# main.net
KiCad netlist of a schematic drawn in EAGLE
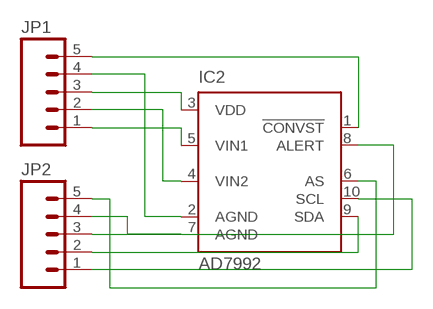
[diagram p0: schematic, sheet 1]

(export (version "E")
  (design (tool "Eeschema 10.0.6"))
  (components
    (comp (ref "IC2")
      (value "AD7992")
      (footprint "eagle-import:MSOP10")
      (fields (field (name "MPN") "AD7992BRMZ-0"))
      (libsource (lib "eagle-import") (part "AD7992"))
    )
    (comp (ref "JP1")
      (value "M05PTH_LONGPADS")
      (footprint "eagle-import:1X05_LONGPADS")
      (libsource (lib "eagle-import") (part "M05PTH_LONGPADS"))
    )
    (comp (ref "JP2")
      (value "M05PTH_LONGPADS")
      (footprint "eagle-import:1X05_LONGPADS")
      (libsource (lib "eagle-import") (part "M05PTH_LONGPADS"))
    )
  )
  (nets
    (net (code "1") (name "Net-(IC2-AGND-Pad2)") (class "Default")
      (node (ref "IC2") (pin "2") (pinfunction "AGND_2") (pintype "power_in"))
      (node (ref "JP1") (pin "4") (pinfunction "4_4") (pintype "passive"))
    )
    (net (code "2") (name "Net-(IC2-AGND-Pad7)") (class "Default")
      (node (ref "IC2") (pin "7") (pinfunction "AGND_7") (pintype "power_in"))
      (node (ref "JP2") (pin "4") (pinfunction "4_4") (pintype "passive"))
    )
    (net (code "3") (name "Net-(IC2-ALERT)") (class "Default")
      (node (ref "IC2") (pin "8") (pinfunction "ALERT_8") (pintype "output"))
      (node (ref "JP2") (pin "3") (pinfunction "3_3") (pintype "passive"))
    )
    (net (code "4") (name "Net-(IC2-AS)") (class "Default")
      (node (ref "IC2") (pin "6") (pinfunction "AS_6") (pintype "input"))
      (node (ref "JP2") (pin "5") (pinfunction "5_5") (pintype "passive"))
    )
    (net (code "5") (name "Net-(IC2-SCL)") (class "Default")
      (node (ref "IC2") (pin "10") (pinfunction "SCL_10") (pintype "input"))
      (node (ref "JP2") (pin "1") (pinfunction "1_1") (pintype "passive"))
    )
    (net (code "6") (name "Net-(IC2-SDA)") (class "Default")
      (node (ref "IC2") (pin "9") (pinfunction "SDA_9") (pintype "bidirectional"))
      (node (ref "JP2") (pin "2") (pinfunction "2_2") (pintype "passive"))
    )
    (net (code "7") (name "Net-(IC2-VDD)") (class "Default")
      (node (ref "IC2") (pin "3") (pinfunction "VDD_3") (pintype "power_in"))
      (node (ref "JP1") (pin "3") (pinfunction "3_3") (pintype "passive"))
    )
    (net (code "8") (name "Net-(IC2-VIN1)") (class "Default")
      (node (ref "IC2") (pin "5") (pinfunction "VIN1_5") (pintype "input"))
      (node (ref "JP1") (pin "1") (pinfunction "1_1") (pintype "passive"))
    )
    (net (code "9") (name "Net-(IC2-VIN2)") (class "Default")
      (node (ref "IC2") (pin "4") (pinfunction "VIN2_4") (pintype "input"))
      (node (ref "JP1") (pin "2") (pinfunction "2_2") (pintype "passive"))
    )
    (net (code "10") (name "Net-(IC2-~{CONVST})") (class "Default")
      (node (ref "IC2") (pin "1") (pinfunction "~{CONVST}_1") (pintype "input"))
      (node (ref "JP1") (pin "5") (pinfunction "5_5") (pintype "passive"))
    )
  )
)
